# EaseEDA_Stand_Kovalenko.net
KiCad netlist of a schematic drawn in EasyEDA
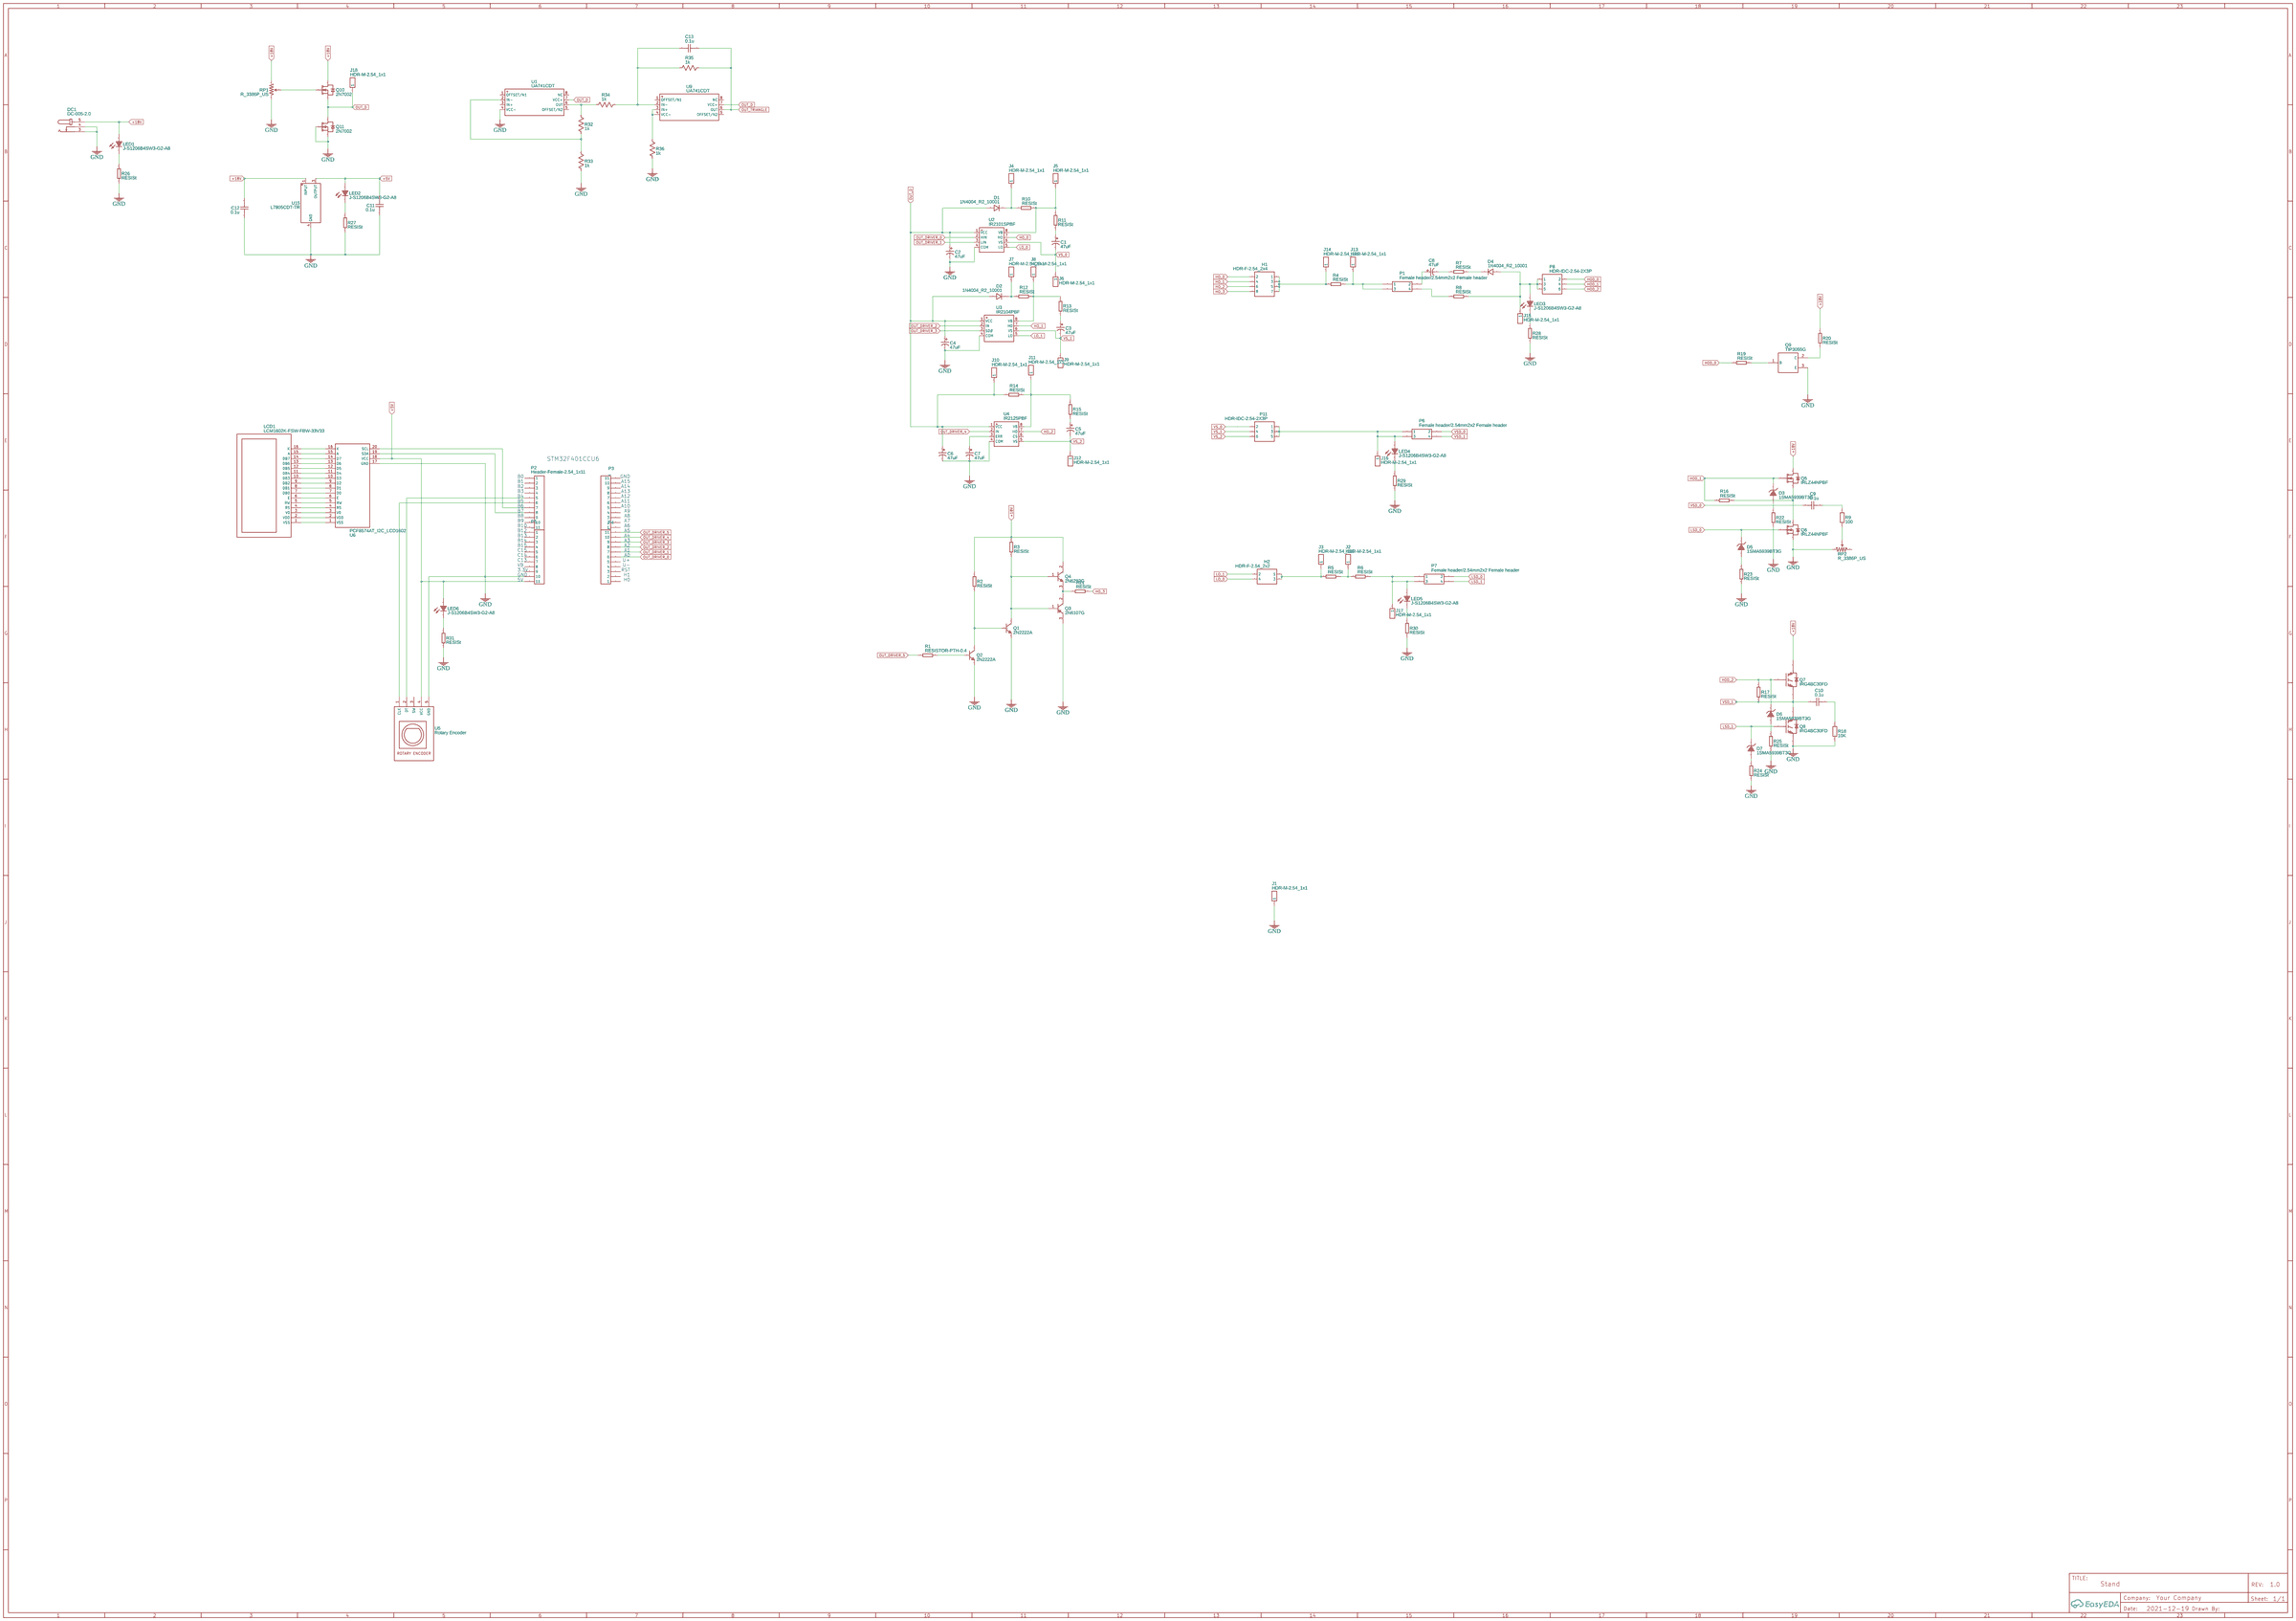
[diagram p0: schematic sheet]

(export (version "E")
  (design (tool "Eeschema 10.0.6"))
  (components
    (comp (ref "C1")
      (value "47uF")
      (fields
        (field (name "BOM_Manufacturer Part") "RD1J476M6L011PC380")
        (field (name "BOM_Supplier Part") "C238012")
      )
      (libsource (lib "") (part "RD1J476M6L011PC380"))
    )
    (comp (ref "C2")
      (value "47uF")
      (fields
        (field (name "BOM_Manufacturer Part") "RD1J476M6L011PC380")
        (field (name "BOM_Supplier Part") "C238012")
      )
      (libsource (lib "") (part "RD1J476M6L011PC380"))
    )
    (comp (ref "C3")
      (value "47uF")
      (fields
        (field (name "BOM_Manufacturer Part") "RD1J476M6L011PC380")
        (field (name "BOM_Supplier Part") "C238012")
      )
      (libsource (lib "") (part "RD1J476M6L011PC380"))
    )
    (comp (ref "C4")
      (value "47uF")
      (fields
        (field (name "BOM_Manufacturer Part") "RD1J476M6L011PC380")
        (field (name "BOM_Supplier Part") "C238012")
      )
      (libsource (lib "") (part "RD1J476M6L011PC380"))
    )
    (comp (ref "C5")
      (value "47uF")
      (fields
        (field (name "BOM_Manufacturer Part") "RD1J476M6L011PC380")
        (field (name "BOM_Supplier Part") "C238012")
      )
      (libsource (lib "") (part "RD1J476M6L011PC380"))
    )
    (comp (ref "C6")
      (value "47uF")
      (fields
        (field (name "BOM_Manufacturer Part") "RD1J476M6L011PC380")
        (field (name "BOM_Supplier Part") "C238012")
      )
      (libsource (lib "") (part "RD1J476M6L011PC380"))
    )
    (comp (ref "C7")
      (value "47uF")
      (fields
        (field (name "BOM_Manufacturer Part") "RD1J476M6L011PC380")
        (field (name "BOM_Supplier Part") "C238012")
      )
      (libsource (lib "") (part "RD1J476M6L011PC380"))
    )
    (comp (ref "C8")
      (value "47uF")
      (fields
        (field (name "BOM_Manufacturer Part") "RD1J476M6L011PC380")
        (field (name "BOM_Supplier Part") "C238012")
      )
      (libsource (lib "") (part "RD1J476M6L011PC380_1"))
    )
    (comp (ref "C9") (value "0.1u") (libsource (lib "") (part "C_0603_US")))
    (comp (ref "C10") (value "0.1u") (libsource (lib "") (part "C_0603_US")))
    (comp (ref "C11") (value "0.1u") (libsource (lib "") (part "C_0603_US_1")))
    (comp (ref "C12") (value "0.1u") (libsource (lib "") (part "C_0603_US_1")))
    (comp (ref "C13") (value "0.1u") (libsource (lib "") (part "C_0603_US_2")))
    (comp (ref "D1")
      (value "1N4004_R2_10001")
      (fields (field (name "BOM_Supplier Part") "C391322"))
      (libsource (lib "") (part "1N4004_R2_10001_1"))
    )
    (comp (ref "D2")
      (value "1N4004_R2_10001")
      (fields (field (name "BOM_Supplier Part") "C391322"))
      (libsource (lib "") (part "1N4004_R2_10001_1"))
    )
    (comp (ref "D3")
      (value "1SMA5939BT3G")
      (fields (field (name "BOM_Supplier Part") "C238874"))
      (libsource (lib "") (part "1SMA5939BT3G"))
    )
    (comp (ref "D4")
      (value "1N4004_R2_10001")
      (fields (field (name "BOM_Supplier Part") "C391322"))
      (libsource (lib "") (part "1N4004_R2_10001"))
    )
    (comp (ref "D5")
      (value "1SMA5939BT3G")
      (fields (field (name "BOM_Supplier Part") "C238874"))
      (libsource (lib "") (part "1SMA5939BT3G"))
    )
    (comp (ref "D6")
      (value "1SMA5939BT3G")
      (fields (field (name "BOM_Supplier Part") "C238874"))
      (libsource (lib "") (part "1SMA5939BT3G"))
    )
    (comp (ref "D7")
      (value "1SMA5939BT3G")
      (fields (field (name "BOM_Supplier Part") "C238874"))
      (libsource (lib "") (part "1SMA5939BT3G"))
    )
    (comp (ref "DC1")
      (value "DC-005-2.0")
      (fields (field (name "BOM_Supplier Part") "C521451"))
      (libsource (lib "") (part "DC-005-2.0"))
    )
    (comp (ref "H1")
      (value "HDR-F-2.54_2x4")
      (fields (field (name "BOM_Supplier Part") "C239344"))
      (libsource (lib "") (part "HDR-F-2.54_2x4"))
    )
    (comp (ref "H2")
      (value "HDR-F-2.54_2x2")
      (fields (field (name "BOM_Supplier Part") "C239342"))
      (libsource (lib "") (part "HDR-F-2.54_2x2"))
    )
    (comp (ref "J1")
      (value "HDR-M-2.54_1x1")
      (fields (field (name "BOM_Supplier Part") "C81276"))
      (libsource (lib "") (part "HDR-M-2.54_1x1"))
    )
    (comp (ref "J2")
      (value "HDR-M-2.54_1x1")
      (fields (field (name "BOM_Supplier Part") "C81276"))
      (libsource (lib "") (part "HDR-M-2.54_1x1"))
    )
    (comp (ref "J3")
      (value "HDR-M-2.54_1x1")
      (fields (field (name "BOM_Supplier Part") "C81276"))
      (libsource (lib "") (part "HDR-M-2.54_1x1"))
    )
    (comp (ref "J4")
      (value "HDR-M-2.54_1x1")
      (fields (field (name "BOM_Supplier Part") "C81276"))
      (libsource (lib "") (part "HDR-M-2.54_1x1"))
    )
    (comp (ref "J5")
      (value "HDR-M-2.54_1x1")
      (fields (field (name "BOM_Supplier Part") "C81276"))
      (libsource (lib "") (part "HDR-M-2.54_1x1"))
    )
    (comp (ref "J6")
      (value "HDR-M-2.54_1x1")
      (fields (field (name "BOM_Supplier Part") "C81276"))
      (libsource (lib "") (part "HDR-M-2.54_1x1_1"))
    )
    (comp (ref "J7")
      (value "HDR-M-2.54_1x1")
      (fields (field (name "BOM_Supplier Part") "C81276"))
      (libsource (lib "") (part "HDR-M-2.54_1x1"))
    )
    (comp (ref "J8")
      (value "HDR-M-2.54_1x1")
      (fields (field (name "BOM_Supplier Part") "C81276"))
      (libsource (lib "") (part "HDR-M-2.54_1x1"))
    )
    (comp (ref "J9")
      (value "HDR-M-2.54_1x1")
      (fields (field (name "BOM_Supplier Part") "C81276"))
      (libsource (lib "") (part "HDR-M-2.54_1x1_1"))
    )
    (comp (ref "J10")
      (value "HDR-M-2.54_1x1")
      (fields (field (name "BOM_Supplier Part") "C81276"))
      (libsource (lib "") (part "HDR-M-2.54_1x1"))
    )
    (comp (ref "J11")
      (value "HDR-M-2.54_1x1")
      (fields (field (name "BOM_Supplier Part") "C81276"))
      (libsource (lib "") (part "HDR-M-2.54_1x1"))
    )
    (comp (ref "J12")
      (value "HDR-M-2.54_1x1")
      (fields (field (name "BOM_Supplier Part") "C81276"))
      (libsource (lib "") (part "HDR-M-2.54_1x1_1"))
    )
    (comp (ref "J13")
      (value "HDR-M-2.54_1x1")
      (fields (field (name "BOM_Supplier Part") "C81276"))
      (libsource (lib "") (part "HDR-M-2.54_1x1"))
    )
    (comp (ref "J14")
      (value "HDR-M-2.54_1x1")
      (fields (field (name "BOM_Supplier Part") "C81276"))
      (libsource (lib "") (part "HDR-M-2.54_1x1"))
    )
    (comp (ref "J15")
      (value "HDR-M-2.54_1x1")
      (fields (field (name "BOM_Supplier Part") "C81276"))
      (libsource (lib "") (part "HDR-M-2.54_1x1_1"))
    )
    (comp (ref "J16")
      (value "HDR-M-2.54_1x1")
      (fields (field (name "BOM_Supplier Part") "C81276"))
      (libsource (lib "") (part "HDR-M-2.54_1x1_1"))
    )
    (comp (ref "J17")
      (value "HDR-M-2.54_1x1")
      (fields (field (name "BOM_Supplier Part") "C81276"))
      (libsource (lib "") (part "HDR-M-2.54_1x1_1"))
    )
    (comp (ref "J18")
      (value "HDR-M-2.54_1x1")
      (fields (field (name "BOM_Supplier Part") "C81276"))
      (libsource (lib "") (part "HDR-M-2.54_1x1"))
    )
    (comp (ref "LCD1")
      (value "LCM1602K-FSW-FBW-33V33")
      (fields (field (name "BOM_Supplier Part") "C83271"))
      (libsource (lib "") (part "LCM1602K-FSW-FBW-33V33"))
    )
    (comp (ref "LED1")
      (value "J-S1206B4SW3-G2-A8")
      (fields (field (name "BOM_Supplier Part") "C2917491"))
      (libsource (lib "") (part "J-S1206B4SW3-G2-A8"))
    )
    (comp (ref "LED2")
      (value "J-S1206B4SW3-G2-A8")
      (fields (field (name "BOM_Supplier Part") "C2917491"))
      (libsource (lib "") (part "J-S1206B4SW3-G2-A8"))
    )
    (comp (ref "LED3")
      (value "J-S1206B4SW3-G2-A8")
      (fields (field (name "BOM_Supplier Part") "C2917491"))
      (libsource (lib "") (part "J-S1206B4SW3-G2-A8"))
    )
    (comp (ref "LED4")
      (value "J-S1206B4SW3-G2-A8")
      (fields (field (name "BOM_Supplier Part") "C2917491"))
      (libsource (lib "") (part "J-S1206B4SW3-G2-A8"))
    )
    (comp (ref "LED5")
      (value "J-S1206B4SW3-G2-A8")
      (fields (field (name "BOM_Supplier Part") "C2917491"))
      (libsource (lib "") (part "J-S1206B4SW3-G2-A8"))
    )
    (comp (ref "LED6")
      (value "J-S1206B4SW3-G2-A8")
      (fields (field (name "BOM_Supplier Part") "C2917491"))
      (libsource (lib "") (part "J-S1206B4SW3-G2-A8"))
    )
    (comp (ref "P1")
      (value "Female header/2.54mm2x2 Female header")
      (fields (field (name "BOM_Supplier Part") "undefined"))
      (libsource (lib "") (part "Female header/2.54mm2x2 Female header"))
    )
    (comp (ref "P2")
      (value "Header-Female-2.54_1x11")
      (fields
        (field (name "BOM_Manufacturer Part") "Header-Female-2.54_1x10")
        (field (name "BOM_Supplier Part") "undefined")
      )
      (libsource (lib "") (part "Header-Female-2.54_1x11"))
    )
    (comp (ref "P3")
      (value "_")
      (fields
        (field (name "BOM_Manufacturer Part") "Header-Female-2.54_1x10")
        (field (name "BOM_Supplier Part") "undefined")
      )
      (libsource (lib "") (part "Header-Female-2.54_1x11_1"))
    )
    (comp (ref "P4")
      (value "_")
      (fields
        (field (name "BOM_Manufacturer Part") "Header-Female-2.54_1x10")
        (field (name "BOM_Supplier Part") "undefined")
      )
      (libsource (lib "") (part "Header-Female-2.54_1x11_1"))
    )
    (comp (ref "P5")
      (value "_")
      (fields
        (field (name "BOM_Manufacturer Part") "Header-Female-2.54_1x10")
        (field (name "BOM_Supplier Part") "undefined")
      )
      (libsource (lib "") (part "Header-Female-2.54_1x11"))
    )
    (comp (ref "P6")
      (value "Female header/2.54mm2x2 Female header")
      (fields (field (name "BOM_Supplier Part") "undefined"))
      (libsource (lib "") (part "Female header/2.54mm2x2 Female header"))
    )
    (comp (ref "P7")
      (value "Female header/2.54mm2x2 Female header")
      (fields (field (name "BOM_Supplier Part") "undefined"))
      (libsource (lib "") (part "Female header/2.54mm2x2 Female header"))
    )
    (comp (ref "P8")
      (value "HDR-IDC-2.54-2X3P")
      (fields
        (field (name "BOM_Manufacturer Part") "2X3 2.54mm IDC Box")
        (field (name "BOM_Supplier Part") "C11214")
      )
      (libsource (lib "") (part "HDR-IDC-2.54-2X3P_1"))
    )
    (comp (ref "P11")
      (value "HDR-IDC-2.54-2X3P")
      (fields
        (field (name "BOM_Manufacturer Part") "2X3 2.54mm IDC Box")
        (field (name "BOM_Supplier Part") "C11214")
      )
      (libsource (lib "") (part "HDR-IDC-2.54-2X3P"))
    )
    (comp (ref "Q1")
      (value "2N2222A")
      (fields (field (name "BOM_Supplier Part") "C358533"))
      (libsource (lib "") (part "2N2222A"))
    )
    (comp (ref "Q2")
      (value "2N2222A")
      (fields (field (name "BOM_Supplier Part") "C358533"))
      (libsource (lib "") (part "2N2222A"))
    )
    (comp (ref "Q3") (value "2N6107G") (libsource (lib "") (part "2N6107G")))
    (comp (ref "Q4") (value "2N6292G") (libsource (lib "") (part "2N6292G")))
    (comp (ref "Q5")
      (value "IRLZ44NPBF")
      (fields (field (name "BOM_Supplier Part") "C38774"))
      (libsource (lib "") (part "IRLZ44NPBF"))
    )
    (comp (ref "Q6")
      (value "IRLZ44NPBF")
      (fields (field (name "BOM_Supplier Part") "C38774"))
      (libsource (lib "") (part "IRLZ44NPBF"))
    )
    (comp (ref "Q7") (value "IRG4BC30FD") (libsource (lib "") (part "IRG4BC30FD")))
    (comp (ref "Q8") (value "IRG4BC30FD") (libsource (lib "") (part "IRG4BC30FD")))
    (comp (ref "Q9") (value "TIP3055G") (libsource (lib "") (part "TIP3055G")))
    (comp (ref "Q10")
      (value "2N7002")
      (fields (field (name "BOM_Manufacturer Part") "2N7002,215") (field (name "BOM_Supplier Part") "C65189"))
      (libsource (lib "") (part "2N7002"))
    )
    (comp (ref "Q11")
      (value "2N7002")
      (fields (field (name "BOM_Manufacturer Part") "2N7002,215") (field (name "BOM_Supplier Part") "C65189"))
      (libsource (lib "") (part "2N7002"))
    )
    (comp (ref "R1") (value "RESISTOR-PTH-0.4") (libsource (lib "") (part "RESISTOR-PTH-0.4_3")))
    (comp (ref "R2") (value "RESISt") (libsource (lib "") (part "RESISTOR-PTH-0.4_2")))
    (comp (ref "R3") (value "RESISt") (libsource (lib "") (part "RESISTOR-PTH-0.4_2")))
    (comp (ref "R4") (value "RESISt") (libsource (lib "") (part "RESISTOR-PTH-0.4_1")))
    (comp (ref "R5") (value "RESISt") (libsource (lib "") (part "RESISTOR-PTH-0.4_1")))
    (comp (ref "R6") (value "RESISt") (libsource (lib "") (part "RESISTOR-PTH-0.4_1")))
    (comp (ref "R7") (value "RESISt") (libsource (lib "") (part "RESISTOR-PTH-0.4_1")))
    (comp (ref "R8") (value "RESISt") (libsource (lib "") (part "RESISTOR-PTH-0.4_1")))
    (comp (ref "R9")
      (value "100")
      (fields
        (field (name "BOM_Manufacturer Part") "EWWR0010J10K0T9")
        (field (name "BOM_Supplier Part") "C349083")
      )
      (libsource (lib "") (part "EWWR0010J10K0T9"))
    )
    (comp (ref "R10") (value "RESISt") (libsource (lib "") (part "RESISTOR-PTH-0.4_3")))
    (comp (ref "R11") (value "RESISt") (libsource (lib "") (part "RESISTOR-PTH-0.4_2")))
    (comp (ref "R12") (value "RESISt") (libsource (lib "") (part "RESISTOR-PTH-0.4_3")))
    (comp (ref "R13") (value "RESISt") (libsource (lib "") (part "RESISTOR-PTH-0.4")))
    (comp (ref "R14") (value "RESISt") (libsource (lib "") (part "RESISTOR-PTH-0.4_3")))
    (comp (ref "R15") (value "RESISt") (libsource (lib "") (part "RESISTOR-PTH-0.4")))
    (comp (ref "R16") (value "RESISt") (libsource (lib "") (part "RESISTOR-PTH-0.4_1")))
    (comp (ref "R17") (value "RESISt") (libsource (lib "") (part "RESISTOR-PTH-0.4")))
    (comp (ref "R18")
      (value "10K")
      (fields
        (field (name "BOM_Manufacturer Part") "EWWR0010J10K0T9")
        (field (name "BOM_Supplier Part") "C349083")
      )
      (libsource (lib "") (part "EWWR0010J10K0T9"))
    )
    (comp (ref "R19") (value "RESISt") (libsource (lib "") (part "RESISTOR-PTH-0.4_1")))
    (comp (ref "R20") (value "RESISt") (libsource (lib "") (part "RESISTOR-PTH-0.4")))
    (comp (ref "R21") (value "RESISt") (libsource (lib "") (part "RESISTOR-PTH-0.4_3")))
    (comp (ref "R22") (value "RESISt") (libsource (lib "") (part "RESISTOR-PTH-0.4")))
    (comp (ref "R23") (value "RESISt") (libsource (lib "") (part "RESISTOR-PTH-0.4")))
    (comp (ref "R24") (value "RESISt") (libsource (lib "") (part "RESISTOR-PTH-0.4")))
    (comp (ref "R25") (value "RESISt") (libsource (lib "") (part "RESISTOR-PTH-0.4")))
    (comp (ref "R26") (value "RESISt") (libsource (lib "") (part "RESISTOR-PTH-0.4")))
    (comp (ref "R27") (value "RESISt") (libsource (lib "") (part "RESISTOR-PTH-0.4")))
    (comp (ref "R28") (value "RESISt") (libsource (lib "") (part "RESISTOR-PTH-0.4")))
    (comp (ref "R29") (value "RESISt") (libsource (lib "") (part "RESISTOR-PTH-0.4")))
    (comp (ref "R30") (value "RESISt") (libsource (lib "") (part "RESISTOR-PTH-0.4")))
    (comp (ref "R31") (value "RESISt") (libsource (lib "") (part "RESISTOR-PTH-0.4")))
    (comp (ref "R32") (value "1k") (libsource (lib "") (part "R_0603_US_2")))
    (comp (ref "R33") (value "1k") (libsource (lib "") (part "R_0603_US_2")))
    (comp (ref "R34") (value "1k") (libsource (lib "") (part "R_0603_US")))
    (comp (ref "R35") (value "1k") (libsource (lib "") (part "R_0603_US")))
    (comp (ref "R36") (value "1k") (libsource (lib "") (part "R_0603_US_1")))
    (comp (ref "RP1") (value "R_3386P_US") (libsource (lib "") (part "R_3386P_US")))
    (comp (ref "RP2") (value "R_3386P_US") (libsource (lib "") (part "R_3386P_US_1")))
    (comp (ref "U1")
      (value "UA741CDT")
      (fields (field (name "BOM_Supplier Part") "C7111"))
      (libsource (lib "") (part "UA741CDT"))
    )
    (comp (ref "U2")
      (value "IR2101SPBF")
      (fields (field (name "BOM_Supplier Part") "C537541"))
      (libsource (lib "") (part "IR2101SPBF"))
    )
    (comp (ref "U3")
      (value "IR2104PBF")
      (fields (field (name "BOM_Supplier Part") "C2959"))
      (libsource (lib "") (part "IR2104PBF"))
    )
    (comp (ref "U4")
      (value "IR2125PBF")
      (fields (field (name "BOM_Supplier Part") "C537562"))
      (libsource (lib "") (part "IR2125PBF"))
    )
    (comp (ref "U5")
      (value "Rotary Encoder")
      (fields (field (name "BOM_Manufacturer Part") "KY-040"))
      (libsource (lib "") (part "Rotary Encoder"))
    )
    (comp (ref "U6")
      (value "PCF8574AT_I2C_LCD1602")
      (fields (field (name "BOM_Manufacturer Part") "PCF8574AT_modul"))
      (libsource (lib "") (part "PCF8574AT_I2C_LCD1602"))
    )
    (comp (ref "U9")
      (value "UA741CDT")
      (fields (field (name "BOM_Supplier Part") "C7111"))
      (libsource (lib "") (part "UA741CDT"))
    )
    (comp (ref "U15")
      (value "L7805CDT-TR")
      (fields (field (name "BOM_Supplier Part") "C310413"))
      (libsource (lib "") (part "L7805CDT-TR"))
    )
  )
  (nets
    (net (code "1") (name "+5V") (class "Default")
      (node (ref "C11") (pin "2") (pinfunction "2_2") (pintype "unspecified"))
      (node (ref "LED2") (pin "2") (pinfunction "A_2") (pintype "input"))
      (node (ref "LED6") (pin "2") (pinfunction "A_2") (pintype "input"))
      (node (ref "P5") (pin "11") (pinfunction "11_11") (pintype "input"))
      (node (ref "U15") (pin "3") (pinfunction "OUTPUT_3") (pintype "unspecified"))
      (node (ref "U5") (pin "4") (pinfunction "VCC_4") (pintype "unspecified"))
      (node (ref "U6") (pin "18") (pinfunction "VCC_18") (pintype "unspecified"))
    )
    (net (code "2") (name "+18V") (class "Default")
      (node (ref "C12") (pin "2") (pinfunction "2_2") (pintype "unspecified"))
      (node (ref "DC1") (pin "5") (pinfunction "5_5") (pintype "unspecified"))
      (node (ref "LED1") (pin "2") (pinfunction "A_2") (pintype "input"))
      (node (ref "Q10") (pin "3") (pinfunction "D_3") (pintype "unspecified"))
      (node (ref "Q4") (pin "2") (pinfunction "C_2") (pintype "unspecified"))
      (node (ref "Q5") (pin "2") (pinfunction "D_2") (pintype "unspecified"))
      (node (ref "Q7") (pin "2") (pinfunction "C_2") (pintype "unspecified"))
      (node (ref "R2") (pin "1") (pinfunction "1_1") (pintype "unspecified"))
      (node (ref "R20") (pin "2") (pinfunction "2_2") (pintype "unspecified"))
      (node (ref "R3") (pin "1") (pinfunction "1_1") (pintype "unspecified"))
      (node (ref "RP1") (pin "1") (pinfunction "1_1") (pintype "unspecified"))
      (node (ref "U15") (pin "1") (pinfunction "INPUT_1") (pintype "unspecified"))
    )
    (net (code "3") (name "GND") (class "Default")
      (node (ref "C11") (pin "1") (pinfunction "1_1") (pintype "unspecified"))
      (node (ref "C12") (pin "1") (pinfunction "1_1") (pintype "unspecified"))
      (node (ref "C2") (pin "2") (pinfunction "2_2") (pintype "input"))
      (node (ref "C4") (pin "2") (pinfunction "2_2") (pintype "input"))
      (node (ref "C6") (pin "2") (pinfunction "2_2") (pintype "input"))
      (node (ref "C7") (pin "2") (pinfunction "2_2") (pintype "input"))
      (node (ref "DC1") (pin "3") (pinfunction "3_3") (pintype "unspecified"))
      (node (ref "DC1") (pin "4") (pinfunction "4_4") (pintype "unspecified"))
      (node (ref "J1") (pin "1") (pinfunction "1_1") (pintype "input"))
      (node (ref "P5") (pin "10") (pinfunction "10_10") (pintype "input"))
      (node (ref "Q1") (pin "3") (pinfunction "E_3") (pintype "unspecified"))
      (node (ref "Q11") (pin "1") (pinfunction "G_1") (pintype "unspecified"))
      (node (ref "Q11") (pin "2") (pinfunction "S_2") (pintype "unspecified"))
      (node (ref "Q2") (pin "3") (pinfunction "E_3") (pintype "unspecified"))
      (node (ref "Q3") (pin "3") (pinfunction "E_3") (pintype "unspecified"))
      (node (ref "Q6") (pin "3") (pinfunction "S_3") (pintype "unspecified"))
      (node (ref "Q8") (pin "3") (pinfunction "E_3") (pintype "unspecified"))
      (node (ref "Q9") (pin "3") (pinfunction "E_3") (pintype "unspecified"))
      (node (ref "R18") (pin "2") (pinfunction "2_2") (pintype "unspecified"))
      (node (ref "R22") (pin "1") (pinfunction "1_1") (pintype "unspecified"))
      (node (ref "R23") (pin "1") (pinfunction "1_1") (pintype "unspecified"))
      (node (ref "R24") (pin "1") (pinfunction "1_1") (pintype "unspecified"))
      (node (ref "R25") (pin "1") (pinfunction "1_1") (pintype "unspecified"))
      (node (ref "R26") (pin "1") (pinfunction "1_1") (pintype "unspecified"))
      (node (ref "R27") (pin "1") (pinfunction "1_1") (pintype "unspecified"))
      (node (ref "R28") (pin "1") (pinfunction "1_1") (pintype "unspecified"))
      (node (ref "R29") (pin "1") (pinfunction "1_1") (pintype "unspecified"))
      (node (ref "R30") (pin "1") (pinfunction "1_1") (pintype "unspecified"))
      (node (ref "R31") (pin "1") (pinfunction "1_1") (pintype "unspecified"))
      (node (ref "R33") (pin "1") (pinfunction "1_1") (pintype "unspecified"))
      (node (ref "R36") (pin "2") (pinfunction "2_2") (pintype "unspecified"))
      (node (ref "RP1") (pin "3") (pinfunction "3_3") (pintype "unspecified"))
      (node (ref "RP2") (pin "1") (pinfunction "1_1") (pintype "unspecified"))
      (node (ref "U1") (pin "4") (pinfunction "VCC-_4") (pintype "unspecified"))
      (node (ref "U15") (pin "4") (pinfunction "GND_4") (pintype "unspecified"))
      (node (ref "U2") (pin "4") (pinfunction "COM_4") (pintype "unspecified"))
      (node (ref "U3") (pin "4") (pinfunction "COM_4") (pintype "unspecified"))
      (node (ref "U4") (pin "4") (pinfunction "COM_4") (pintype "unspecified"))
      (node (ref "U5") (pin "5") (pinfunction "GND_5") (pintype "unspecified"))
      (node (ref "U6") (pin "17") (pinfunction "GND_17") (pintype "unspecified"))
    )
    (net (code "4") (name "HOD_0") (class "Default")
      (node (ref "P8") (pin "2") (pinfunction "2_2") (pintype "unspecified"))
      (node (ref "R19") (pin "2") (pinfunction "2_2") (pintype "unspecified"))
    )
    (net (code "5") (name "HOD_1") (class "Default")
      (node (ref "D3") (pin "1") (pinfunction "C_1") (pintype "unspecified"))
      (node (ref "P8") (pin "4") (pinfunction "4_4") (pintype "unspecified"))
      (node (ref "Q5") (pin "1") (pinfunction "G_1") (pintype "unspecified"))
      (node (ref "R16") (pin "2") (pinfunction "2_2") (pintype "unspecified"))
    )
    (net (code "6") (name "HOD_2") (class "Default")
      (node (ref "D6") (pin "1") (pinfunction "C_1") (pintype "unspecified"))
      (node (ref "P8") (pin "6") (pinfunction "6_6") (pintype "unspecified"))
      (node (ref "Q7") (pin "1") (pinfunction "G_1") (pintype "unspecified"))
      (node (ref "R17") (pin "2") (pinfunction "2_2") (pintype "unspecified"))
    )
    (net (code "7") (name "HO_0") (class "Default")
      (node (ref "H1") (pin "2") (pinfunction "2_2") (pintype "unspecified"))
      (node (ref "U2") (pin "7") (pinfunction "HO_7") (pintype "unspecified"))
    )
    (net (code "8") (name "HO_1") (class "Default")
      (node (ref "H1") (pin "4") (pinfunction "4_4") (pintype "unspecified"))
      (node (ref "U3") (pin "7") (pinfunction "HO_7") (pintype "unspecified"))
    )
    (net (code "9") (name "HO_2") (class "Default")
      (node (ref "H1") (pin "6") (pinfunction "6_6") (pintype "unspecified"))
      (node (ref "U4") (pin "7") (pinfunction "HO_7") (pintype "unspecified"))
    )
    (net (code "10") (name "HO_3") (class "Default")
      (node (ref "H1") (pin "8") (pinfunction "8_8") (pintype "unspecified"))
      (node (ref "R21") (pin "2") (pinfunction "2_2") (pintype "unspecified"))
    )
    (net (code "11") (name "LO_0") (class "Default")
      (node (ref "H2") (pin "4") (pinfunction "4_4") (pintype "unspecified"))
      (node (ref "U2") (pin "5") (pinfunction "LO_5") (pintype "unspecified"))
    )
    (net (code "12") (name "LO_1") (class "Default")
      (node (ref "H2") (pin "2") (pinfunction "2_2") (pintype "unspecified"))
      (node (ref "U3") (pin "5") (pinfunction "LO_5") (pintype "unspecified"))
    )
    (net (code "13") (name "LSD_0") (class "Default")
      (node (ref "D5") (pin "1") (pinfunction "C_1") (pintype "unspecified"))
      (node (ref "P7") (pin "2") (pinfunction "2_2") (pintype "input"))
      (node (ref "Q6") (pin "1") (pinfunction "G_1") (pintype "unspecified"))
    )
    (net (code "14") (name "LSD_1") (class "Default")
      (node (ref "D7") (pin "1") (pinfunction "C_1") (pintype "unspecified"))
      (node (ref "P7") (pin "4") (pinfunction "4_4") (pintype "input"))
      (node (ref "Q8") (pin "1") (pinfunction "G_1") (pintype "unspecified"))
    )
    (net (code "15") (name "Net-(C1-Pad1)") (class "Default")
      (node (ref "C1") (pin "1") (pinfunction "1_1") (pintype "input"))
      (node (ref "R11") (pin "2") (pinfunction "2_2") (pintype "unspecified"))
    )
    (net (code "16") (name "Net-(C3-Pad1)") (class "Default")
      (node (ref "C3") (pin "1") (pinfunction "1_1") (pintype "input"))
      (node (ref "R13") (pin "1") (pinfunction "1_1") (pintype "unspecified"))
    )
    (net (code "17") (name "Net-(C5-Pad1)") (class "Default")
      (node (ref "C5") (pin "1") (pinfunction "1_1") (pintype "input"))
      (node (ref "R15") (pin "1") (pinfunction "1_1") (pintype "unspecified"))
    )
    (net (code "18") (name "Net-(C8-Pad1)") (class "Default")
      (node (ref "C8") (pin "1") (pinfunction "1_1") (pintype "input"))
      (node (ref "P1") (pin "2") (pinfunction "2_2") (pintype "input"))
    )
    (net (code "19") (name "Net-(C8-Pad2)") (class "Default")
      (node (ref "C8") (pin "2") (pinfunction "2_2") (pintype "input"))
      (node (ref "R7") (pin "2") (pinfunction "2_2") (pintype "unspecified"))
    )
    (net (code "20") (name "Net-(C9-Pad2)") (class "Default")
      (node (ref "C9") (pin "2") (pinfunction "2_2") (pintype "unspecified"))
      (node (ref "R9") (pin "1") (pinfunction "1_1") (pintype "unspecified"))
    )
    (net (code "21") (name "Net-(C10-Pad2)") (class "Default")
      (node (ref "C10") (pin "2") (pinfunction "2_2") (pintype "unspecified"))
      (node (ref "R18") (pin "1") (pinfunction "1_1") (pintype "unspecified"))
    )
    (net (code "22") (name "Net-(D1-C)") (class "Default")
      (node (ref "D1") (pin "1") (pinfunction "C_1") (pintype "unspecified"))
      (node (ref "J4") (pin "1") (pinfunction "1_1") (pintype "input"))
      (node (ref "R10") (pin "1") (pinfunction "1_1") (pintype "unspecified"))
    )
    (net (code "23") (name "Net-(D2-C)") (class "Default")
      (node (ref "D2") (pin "1") (pinfunction "C_1") (pintype "unspecified"))
      (node (ref "J7") (pin "1") (pinfunction "1_1") (pintype "input"))
      (node (ref "R12") (pin "1") (pinfunction "1_1") (pintype "unspecified"))
    )
    (net (code "24") (name "Net-(D3-A)") (class "Default")
      (node (ref "D3") (pin "2") (pinfunction "A_2") (pintype "unspecified"))
      (node (ref "R22") (pin "2") (pinfunction "2_2") (pintype "unspecified"))
    )
    (net (code "25") (name "Net-(D4-A)") (class "Default")
      (node (ref "D4") (pin "2") (pinfunction "A_2") (pintype "unspecified"))
      (node (ref "J15") (pin "1") (pinfunction "1_1") (pintype "input"))
      (node (ref "LED3") (pin "2") (pinfunction "A_2") (pintype "input"))
      (node (ref "P8") (pin "1") (pinfunction "1_1") (pintype "unspecified"))
      (node (ref "P8") (pin "3") (pinfunction "3_3") (pintype "unspecified"))
      (node (ref "P8") (pin "5") (pinfunction "5_5") (pintype "unspecified"))
      (node (ref "R8") (pin "1") (pinfunction "1_1") (pintype "unspecified"))
    )
    (net (code "26") (name "Net-(D4-C)") (class "Default")
      (node (ref "D4") (pin "1") (pinfunction "C_1") (pintype "unspecified"))
      (node (ref "R7") (pin "1") (pinfunction "1_1") (pintype "unspecified"))
    )
    (net (code "27") (name "Net-(D5-A)") (class "Default")
      (node (ref "D5") (pin "2") (pinfunction "A_2") (pintype "unspecified"))
      (node (ref "R23") (pin "2") (pinfunction "2_2") (pintype "unspecified"))
    )
    (net (code "28") (name "Net-(D6-A)") (class "Default")
      (node (ref "D6") (pin "2") (pinfunction "A_2") (pintype "unspecified"))
      (node (ref "R25") (pin "2") (pinfunction "2_2") (pintype "unspecified"))
    )
    (net (code "29") (name "Net-(D7-A)") (class "Default")
      (node (ref "D7") (pin "2") (pinfunction "A_2") (pintype "unspecified"))
      (node (ref "R24") (pin "2") (pinfunction "2_2") (pintype "unspecified"))
    )
    (net (code "30") (name "Net-(H1-Pad1)") (class "Default")
      (node (ref "H1") (pin "1") (pinfunction "1_1") (pintype "unspecified"))
      (node (ref "H1") (pin "3") (pinfunction "3_3") (pintype "unspecified"))
      (node (ref "H1") (pin "5") (pinfunction "5_5") (pintype "unspecified"))
      (node (ref "H1") (pin "7") (pinfunction "7_7") (pintype "unspecified"))
      (node (ref "J14") (pin "1") (pinfunction "1_1") (pintype "input"))
      (node (ref "R4") (pin "2") (pinfunction "2_2") (pintype "unspecified"))
    )
    (net (code "31") (name "Net-(H2-Pad1)") (class "Default")
      (node (ref "H2") (pin "1") (pinfunction "1_1") (pintype "unspecified"))
      (node (ref "H2") (pin "3") (pinfunction "3_3") (pintype "unspecified"))
      (node (ref "J3") (pin "1") (pinfunction "1_1") (pintype "input"))
      (node (ref "R5") (pin "2") (pinfunction "2_2") (pintype "unspecified"))
    )
    (net (code "32") (name "Net-(J2-Pad1)") (class "Default")
      (node (ref "J2") (pin "1") (pinfunction "1_1") (pintype "input"))
      (node (ref "R5") (pin "1") (pinfunction "1_1") (pintype "unspecified"))
      (node (ref "R6") (pin "2") (pinfunction "2_2") (pintype "unspecified"))
    )
    (net (code "33") (name "Net-(J13-Pad1)") (class "Default")
      (node (ref "J13") (pin "1") (pinfunction "1_1") (pintype "input"))
      (node (ref "P1") (pin "1") (pinfunction "1_1") (pintype "input"))
      (node (ref "P1") (pin "3") (pinfunction "3_3") (pintype "input"))
      (node (ref "R4") (pin "1") (pinfunction "1_1") (pintype "unspecified"))
    )
    (net (code "34") (name "Net-(LCD1-A)") (class "Default")
      (node (ref "LCD1") (pin "15") (pinfunction "A_15") (pintype "unspecified"))
      (node (ref "U6") (pin "15") (pinfunction "A_15") (pintype "unspecified"))
    )
    (net (code "35") (name "Net-(LCD1-DB0)") (class "Default")
      (node (ref "LCD1") (pin "7") (pinfunction "DB0_7") (pintype "unspecified"))
      (node (ref "U6") (pin "7") (pinfunction "D0_7") (pintype "unspecified"))
    )
    (net (code "36") (name "Net-(LCD1-DB1)") (class "Default")
      (node (ref "LCD1") (pin "8") (pinfunction "DB1_8") (pintype "unspecified"))
      (node (ref "U6") (pin "8") (pinfunction "D1_8") (pintype "unspecified"))
    )
    (net (code "37") (name "Net-(LCD1-DB2)") (class "Default")
      (node (ref "LCD1") (pin "9") (pinfunction "DB2_9") (pintype "unspecified"))
      (node (ref "U6") (pin "9") (pinfunction "D2_9") (pintype "unspecified"))
    )
    (net (code "38") (name "Net-(LCD1-DB3)") (class "Default")
      (node (ref "LCD1") (pin "10") (pinfunction "DB3_10") (pintype "unspecified"))
      (node (ref "U6") (pin "10") (pinfunction "D3_10") (pintype "unspecified"))
    )
    (net (code "39") (name "Net-(LCD1-DB4)") (class "Default")
      (node (ref "LCD1") (pin "11") (pinfunction "DB4_11") (pintype "unspecified"))
      (node (ref "U6") (pin "11") (pinfunction "D4_11") (pintype "unspecified"))
    )
    (net (code "40") (name "Net-(LCD1-DB5)") (class "Default")
      (node (ref "LCD1") (pin "12") (pinfunction "DB5_12") (pintype "unspecified"))
      (node (ref "U6") (pin "12") (pinfunction "D5_12") (pintype "unspecified"))
    )
    (net (code "41") (name "Net-(LCD1-DB6)") (class "Default")
      (node (ref "LCD1") (pin "13") (pinfunction "DB6_13") (pintype "unspecified"))
      (node (ref "U6") (pin "13") (pinfunction "D6_13") (pintype "unspecified"))
    )
    (net (code "42") (name "Net-(LCD1-DB7)") (class "Default")
      (node (ref "LCD1") (pin "14") (pinfunction "DB7_14") (pintype "unspecified"))
      (node (ref "U6") (pin "14") (pinfunction "D7_14") (pintype "unspecified"))
    )
    (net (code "43") (name "Net-(LCD1-E)") (class "Default")
      (node (ref "LCD1") (pin "6") (pinfunction "E_6") (pintype "unspecified"))
      (node (ref "U6") (pin "6") (pinfunction "E_6") (pintype "unspecified"))
    )
    (net (code "44") (name "Net-(LCD1-K)") (class "Default")
      (node (ref "LCD1") (pin "16") (pinfunction "K_16") (pintype "unspecified"))
      (node (ref "U6") (pin "16") (pinfunction "K_16") (pintype "unspecified"))
    )
    (net (code "45") (name "Net-(LCD1-RS)") (class "Default")
      (node (ref "LCD1") (pin "4") (pinfunction "RS_4") (pintype "unspecified"))
      (node (ref "U6") (pin "4") (pinfunction "RS_4") (pintype "unspecified"))
    )
    (net (code "46") (name "Net-(LCD1-RW)") (class "Default")
      (node (ref "LCD1") (pin "5") (pinfunction "RW_5") (pintype "unspecified"))
      (node (ref "U6") (pin "5") (pinfunction "RW_5") (pintype "unspecified"))
    )
    (net (code "47") (name "Net-(LCD1-V0)") (class "Default")
      (node (ref "LCD1") (pin "3") (pinfunction "V0_3") (pintype "unspecified"))
      (node (ref "U6") (pin "3") (pinfunction "V0_3") (pintype "unspecified"))
    )
    (net (code "48") (name "Net-(LCD1-VDD)") (class "Default")
      (node (ref "LCD1") (pin "2") (pinfunction "VDD_2") (pintype "unspecified"))
      (node (ref "U6") (pin "2") (pinfunction "VDD_2") (pintype "unspecified"))
    )
    (net (code "49") (name "Net-(LCD1-VSS)") (class "Default")
      (node (ref "LCD1") (pin "1") (pinfunction "VSS_1") (pintype "unspecified"))
      (node (ref "U6") (pin "1") (pinfunction "VSS_1") (pintype "unspecified"))
    )
    (net (code "50") (name "Net-(LED1-K)") (class "Default")
      (node (ref "LED1") (pin "1") (pinfunction "K_1") (pintype "input"))
      (node (ref "R26") (pin "2") (pinfunction "2_2") (pintype "unspecified"))
    )
    (net (code "51") (name "Net-(LED2-K)") (class "Default")
      (node (ref "LED2") (pin "1") (pinfunction "K_1") (pintype "input"))
      (node (ref "R27") (pin "2") (pinfunction "2_2") (pintype "unspecified"))
    )
    (net (code "52") (name "Net-(LED3-K)") (class "Default")
      (node (ref "LED3") (pin "1") (pinfunction "K_1") (pintype "input"))
      (node (ref "R28") (pin "2") (pinfunction "2_2") (pintype "unspecified"))
    )
    (net (code "53") (name "Net-(LED4-A)") (class "Default")
      (node (ref "J16") (pin "1") (pinfunction "1_1") (pintype "input"))
      (node (ref "LED4") (pin "2") (pinfunction "A_2") (pintype "input"))
      (node (ref "P11") (pin "1") (pinfunction "1_1") (pintype "unspecified"))
      (node (ref "P11") (pin "3") (pinfunction "3_3") (pintype "unspecified"))
      (node (ref "P11") (pin "5") (pinfunction "5_5") (pintype "unspecified"))
      (node (ref "P6") (pin "1") (pinfunction "1_1") (pintype "input"))
      (node (ref "P6") (pin "3") (pinfunction "3_3") (pintype "input"))
    )
    (net (code "54") (name "Net-(LED4-K)") (class "Default")
      (node (ref "LED4") (pin "1") (pinfunction "K_1") (pintype "input"))
      (node (ref "R29") (pin "2") (pinfunction "2_2") (pintype "unspecified"))
    )
    (net (code "55") (name "Net-(LED5-A)") (class "Default")
      (node (ref "J17") (pin "1") (pinfunction "1_1") (pintype "input"))
      (node (ref "LED5") (pin "2") (pinfunction "A_2") (pintype "input"))
      (node (ref "P7") (pin "1") (pinfunction "1_1") (pintype "input"))
      (node (ref "P7") (pin "3") (pinfunction "3_3") (pintype "input"))
      (node (ref "R6") (pin "1") (pinfunction "1_1") (pintype "unspecified"))
    )
    (net (code "56") (name "Net-(LED5-K)") (class "Default")
      (node (ref "LED5") (pin "1") (pinfunction "K_1") (pintype "input"))
      (node (ref "R30") (pin "2") (pinfunction "2_2") (pintype "unspecified"))
    )
    (net (code "57") (name "Net-(LED6-K)") (class "Default")
      (node (ref "LED6") (pin "1") (pinfunction "K_1") (pintype "input"))
      (node (ref "R31") (pin "2") (pinfunction "2_2") (pintype "unspecified"))
    )
    (net (code "58") (name "Net-(P1-Pad4)") (class "Default")
      (node (ref "P1") (pin "4") (pinfunction "4_4") (pintype "input"))
      (node (ref "R8") (pin "2") (pinfunction "2_2") (pintype "unspecified"))
    )
    (net (code "59") (name "Net-(Q1-B)") (class "Default")
      (node (ref "Q1") (pin "2") (pinfunction "B_2") (pintype "unspecified"))
      (node (ref "Q2") (pin "1") (pinfunction "C_1") (pintype "unspecified"))
      (node (ref "R2") (pin "2") (pinfunction "2_2") (pintype "unspecified"))
    )
    (net (code "60") (name "Net-(Q1-C)") (class "Default")
      (node (ref "Q1") (pin "1") (pinfunction "C_1") (pintype "unspecified"))
      (node (ref "Q3") (pin "1") (pinfunction "B_1") (pintype "unspecified"))
      (node (ref "Q4") (pin "1") (pinfunction "B_1") (pintype "unspecified"))
      (node (ref "R3") (pin "2") (pinfunction "2_2") (pintype "unspecified"))
    )
    (net (code "61") (name "Net-(Q2-B)") (class "Default")
      (node (ref "Q2") (pin "2") (pinfunction "B_2") (pintype "unspecified"))
      (node (ref "R1") (pin "2") (pinfunction "2_2") (pintype "unspecified"))
    )
    (net (code "62") (name "Net-(Q3-C)") (class "Default")
      (node (ref "Q3") (pin "2") (pinfunction "C_2") (pintype "unspecified"))
      (node (ref "Q4") (pin "3") (pinfunction "E_3") (pintype "unspecified"))
      (node (ref "R21") (pin "1") (pinfunction "1_1") (pintype "unspecified"))
    )
    (net (code "63") (name "Net-(Q5-S)") (class "Default")
      (node (ref "Q5") (pin "3") (pinfunction "S_3") (pintype "unspecified"))
      (node (ref "Q6") (pin "2") (pinfunction "D_2") (pintype "unspecified"))
      (node (ref "R16") (pin "1") (pinfunction "1_1") (pintype "unspecified"))
    )
    (net (code "64") (name "Net-(Q9-B)") (class "Default")
      (node (ref "Q9") (pin "1") (pinfunction "B_1") (pintype "unspecified"))
      (node (ref "R19") (pin "1") (pinfunction "1_1") (pintype "unspecified"))
    )
    (net (code "65") (name "Net-(Q9-C)") (class "Default")
      (node (ref "Q9") (pin "2") (pinfunction "C_2") (pintype "unspecified"))
      (node (ref "R20") (pin "1") (pinfunction "1_1") (pintype "unspecified"))
    )
    (net (code "66") (name "Net-(Q10-G)") (class "Default")
      (node (ref "Q10") (pin "1") (pinfunction "G_1") (pintype "unspecified"))
      (node (ref "RP1") (pin "2") (pinfunction "2_2") (pintype "unspecified"))
    )
    (net (code "67") (name "Net-(R9-Pad2)") (class "Default")
      (node (ref "R9") (pin "2") (pinfunction "2_2") (pintype "unspecified"))
      (node (ref "RP2") (pin "2") (pinfunction "2_2") (pintype "unspecified"))
    )
    (net (code "68") (name "Net-(U1-IN-)") (class "Default")
      (node (ref "R32") (pin "1") (pinfunction "1_1") (pintype "unspecified"))
      (node (ref "R33") (pin "2") (pinfunction "2_2") (pintype "unspecified"))
      (node (ref "U1") (pin "2") (pinfunction "IN-_2") (pintype "unspecified"))
    )
    (net (code "69") (name "Net-(U1-OUT)") (class "Default")
      (node (ref "R32") (pin "2") (pinfunction "2_2") (pintype "unspecified"))
      (node (ref "R34") (pin "2") (pinfunction "2_2") (pintype "unspecified"))
      (node (ref "U1") (pin "6") (pinfunction "OUT_6") (pintype "unspecified"))
    )
    (net (code "70") (name "Net-(U2-VB)") (class "Default")
      (node (ref "J5") (pin "1") (pinfunction "1_1") (pintype "input"))
      (node (ref "R10") (pin "2") (pinfunction "2_2") (pintype "unspecified"))
      (node (ref "R11") (pin "1") (pinfunction "1_1") (pintype "unspecified"))
      (node (ref "U2") (pin "8") (pinfunction "VB_8") (pintype "unspecified"))
    )
    (net (code "71") (name "Net-(U3-VB)") (class "Default")
      (node (ref "J8") (pin "1") (pinfunction "1_1") (pintype "input"))
      (node (ref "R12") (pin "2") (pinfunction "2_2") (pintype "unspecified"))
      (node (ref "R13") (pin "2") (pinfunction "2_2") (pintype "unspecified"))
      (node (ref "U3") (pin "8") (pinfunction "VB_8") (pintype "unspecified"))
    )
    (net (code "72") (name "Net-(U4-ERR)") (class "Default")
      (node (ref "C7") (pin "1") (pinfunction "1_1") (pintype "input"))
      (node (ref "U4") (pin "3") (pinfunction "ERR_3") (pintype "unspecified"))
    )
    (net (code "73") (name "Net-(U4-VB)") (class "Default")
      (node (ref "J11") (pin "1") (pinfunction "1_1") (pintype "input"))
      (node (ref "R14") (pin "2") (pinfunction "2_2") (pintype "unspecified"))
      (node (ref "R15") (pin "2") (pinfunction "2_2") (pintype "unspecified"))
      (node (ref "U4") (pin "8") (pinfunction "VB_8") (pintype "unspecified"))
    )
    (net (code "74") (name "Net-(U5-CLK)") (class "Default")
      (node (ref "P2") (pin "6") (pinfunction "6_6") (pintype "input"))
      (node (ref "U5") (pin "1") (pinfunction "CLK_1") (pintype "unspecified"))
    )
    (net (code "75") (name "Net-(U5-DT)") (class "Default")
      (node (ref "P2") (pin "5") (pinfunction "5_5") (pintype "input"))
      (node (ref "U5") (pin "2") (pinfunction "DT_2") (pintype "unspecified"))
    )
    (net (code "76") (name "Net-(U6-SCL)") (class "Default")
      (node (ref "P2") (pin "7") (pinfunction "7_7") (pintype "input"))
      (node (ref "U6") (pin "20") (pinfunction "SCL_20") (pintype "unspecified"))
    )
    (net (code "77") (name "Net-(U6-SDA)") (class "Default")
      (node (ref "P2") (pin "8") (pinfunction "8_8") (pintype "input"))
      (node (ref "U6") (pin "19") (pinfunction "SDA_19") (pintype "unspecified"))
    )
    (net (code "78") (name "Net-(U9-IN+)") (class "Default")
      (node (ref "R36") (pin "1") (pinfunction "1_1") (pintype "unspecified"))
      (node (ref "U9") (pin "3") (pinfunction "IN+_3") (pintype "unspecified"))
      (node (ref "U9") (pin "4") (pinfunction "VCC-_4") (pintype "unspecified"))
    )
    (net (code "79") (name "Net-(U9-IN-)") (class "Default")
      (node (ref "C13") (pin "2") (pinfunction "2_2") (pintype "unspecified"))
      (node (ref "R34") (pin "1") (pinfunction "1_1") (pintype "unspecified"))
      (node (ref "R35") (pin "2") (pinfunction "2_2") (pintype "unspecified"))
      (node (ref "U9") (pin "2") (pinfunction "IN-_2") (pintype "unspecified"))
    )
    (net (code "80") (name "OUT_D") (class "Default")
      (node (ref "C2") (pin "1") (pinfunction "1_1") (pintype "input"))
      (node (ref "C4") (pin "1") (pinfunction "1_1") (pintype "input"))
      (node (ref "C6") (pin "1") (pinfunction "1_1") (pintype "input"))
      (node (ref "D1") (pin "2") (pinfunction "A_2") (pintype "unspecified"))
      (node (ref "D2") (pin "2") (pinfunction "A_2") (pintype "unspecified"))
      (node (ref "J10") (pin "1") (pinfunction "1_1") (pintype "input"))
      (node (ref "J18") (pin "1") (pinfunction "1_1") (pintype "input"))
      (node (ref "Q10") (pin "2") (pinfunction "S_2") (pintype "unspecified"))
      (node (ref "Q11") (pin "3") (pinfunction "D_3") (pintype "unspecified"))
      (node (ref "R14") (pin "1") (pinfunction "1_1") (pintype "unspecified"))
      (node (ref "U1") (pin "7") (pinfunction "VCC+_7") (pintype "unspecified"))
      (node (ref "U2") (pin "1") (pinfunction "VCC_1") (pintype "unspecified"))
      (node (ref "U3") (pin "1") (pinfunction "VCC_1") (pintype "unspecified"))
      (node (ref "U4") (pin "1") (pinfunction "VCC_1") (pintype "unspecified"))
      (node (ref "U9") (pin "7") (pinfunction "VCC+_7") (pintype "unspecified"))
    )
    (net (code "81") (name "OUT_DRIVER_0") (class "Default")
      (node (ref "P4") (pin "6") (pinfunction "6_6") (pintype "input"))
      (node (ref "U2") (pin "2") (pinfunction "HIN_2") (pintype "unspecified"))
    )
    (net (code "82") (name "OUT_DRIVER_1") (class "Default")
      (node (ref "P4") (pin "7") (pinfunction "7_7") (pintype "input"))
      (node (ref "U2") (pin "3") (pinfunction "LIN_3") (pintype "unspecified"))
    )
    (net (code "83") (name "OUT_DRIVER_2") (class "Default")
      (node (ref "P4") (pin "8") (pinfunction "8_8") (pintype "input"))
      (node (ref "U3") (pin "2") (pinfunction "IN_2") (pintype "unspecified"))
    )
    (net (code "84") (name "OUT_DRIVER_3") (class "Default")
      (node (ref "P4") (pin "9") (pinfunction "9_9") (pintype "input"))
      (node (ref "U3") (pin "3") (pinfunction "SD#_3") (pintype "unspecified"))
    )
    (net (code "85") (name "OUT_DRIVER_4") (class "Default")
      (node (ref "P4") (pin "10") (pinfunction "10_10") (pintype "input"))
      (node (ref "U4") (pin "2") (pinfunction "IN_2") (pintype "unspecified"))
    )
    (net (code "86") (name "OUT_DRIVER_5") (class "Default")
      (node (ref "P4") (pin "11") (pinfunction "11_11") (pintype "input"))
      (node (ref "R1") (pin "1") (pinfunction "1_1") (pintype "unspecified"))
    )
    (net (code "87") (name "OUT_TRIANGLE") (class "Default")
      (node (ref "C13") (pin "1") (pinfunction "1_1") (pintype "unspecified"))
      (node (ref "R35") (pin "1") (pinfunction "1_1") (pintype "unspecified"))
      (node (ref "U9") (pin "6") (pinfunction "OUT_6") (pintype "unspecified"))
    )
    (net (code "88") (name "VSD_0") (class "Default")
      (node (ref "C9") (pin "1") (pinfunction "1_1") (pintype "unspecified"))
      (node (ref "P6") (pin "2") (pinfunction "2_2") (pintype "input"))
    )
    (net (code "89") (name "VSD_1") (class "Default")
      (node (ref "C10") (pin "1") (pinfunction "1_1") (pintype "unspecified"))
      (node (ref "P6") (pin "4") (pinfunction "4_4") (pintype "input"))
      (node (ref "Q7") (pin "3") (pinfunction "E_3") (pintype "unspecified"))
      (node (ref "Q8") (pin "2") (pinfunction "C_2") (pintype "unspecified"))
      (node (ref "R17") (pin "1") (pinfunction "1_1") (pintype "unspecified"))
    )
    (net (code "90") (name "VS_0") (class "Default")
      (node (ref "C1") (pin "2") (pinfunction "2_2") (pintype "input"))
      (node (ref "J6") (pin "1") (pinfunction "1_1") (pintype "input"))
      (node (ref "P11") (pin "2") (pinfunction "2_2") (pintype "unspecified"))
      (node (ref "U2") (pin "6") (pinfunction "VS_6") (pintype "unspecified"))
    )
    (net (code "91") (name "VS_1") (class "Default")
      (node (ref "C3") (pin "2") (pinfunction "2_2") (pintype "input"))
      (node (ref "J9") (pin "1") (pinfunction "1_1") (pintype "input"))
      (node (ref "P11") (pin "4") (pinfunction "4_4") (pintype "unspecified"))
      (node (ref "U3") (pin "6") (pinfunction "VS_6") (pintype "unspecified"))
    )
    (net (code "92") (name "VS_2") (class "Default")
      (node (ref "C5") (pin "2") (pinfunction "2_2") (pintype "input"))
      (node (ref "J12") (pin "1") (pinfunction "1_1") (pintype "input"))
      (node (ref "P11") (pin "6") (pinfunction "6_6") (pintype "unspecified"))
      (node (ref "U4") (pin "5") (pinfunction "VS_5") (pintype "unspecified"))
    )
    (net (code "93") (name "unconnected-(P2-Pad1)") (class "Default")
      (node (ref "P2") (pin "1") (pinfunction "1_1") (pintype "input"))
    )
    (net (code "94") (name "unconnected-(P2-Pad2)") (class "Default")
      (node (ref "P2") (pin "2") (pinfunction "2_2") (pintype "input"))
    )
    (net (code "95") (name "unconnected-(P2-Pad3)") (class "Default")
      (node (ref "P2") (pin "3") (pinfunction "3_3") (pintype "input"))
    )
    (net (code "96") (name "unconnected-(P2-Pad4)") (class "Default")
      (node (ref "P2") (pin "4") (pinfunction "4_4") (pintype "input"))
    )
    (net (code "97") (name "unconnected-(P2-Pad9)") (class "Default")
      (node (ref "P2") (pin "9") (pinfunction "9_9") (pintype "input"))
    )
    (net (code "98") (name "unconnected-(P2-Pad10)") (class "Default")
      (node (ref "P2") (pin "10") (pinfunction "10_10") (pintype "input"))
    )
    (net (code "99") (name "unconnected-(P2-Pad11)") (class "Default")
      (node (ref "P2") (pin "11") (pinfunction "11_11") (pintype "input"))
    )
    (net (code "100") (name "unconnected-(P3-Pad1)") (class "Default")
      (node (ref "P3") (pin "1") (pinfunction "1_1") (pintype "input"))
    )
    (net (code "101") (name "unconnected-(P3-Pad2)") (class "Default")
      (node (ref "P3") (pin "2") (pinfunction "2_2") (pintype "input"))
    )
    (net (code "102") (name "unconnected-(P3-Pad3)") (class "Default")
      (node (ref "P3") (pin "3") (pinfunction "3_3") (pintype "input"))
    )
    (net (code "103") (name "unconnected-(P3-Pad4)") (class "Default")
      (node (ref "P3") (pin "4") (pinfunction "4_4") (pintype "input"))
    )
    (net (code "104") (name "unconnected-(P3-Pad5)") (class "Default")
      (node (ref "P3") (pin "5") (pinfunction "5_5") (pintype "input"))
    )
    (net (code "105") (name "unconnected-(P3-Pad6)") (class "Default")
      (node (ref "P3") (pin "6") (pinfunction "6_6") (pintype "input"))
    )
    (net (code "106") (name "unconnected-(P3-Pad7)") (class "Default")
      (node (ref "P3") (pin "7") (pinfunction "7_7") (pintype "input"))
    )
    (net (code "107") (name "unconnected-(P3-Pad8)") (class "Default")
      (node (ref "P3") (pin "8") (pinfunction "8_8") (pintype "input"))
    )
    (net (code "108") (name "unconnected-(P3-Pad9)") (class "Default")
      (node (ref "P3") (pin "9") (pinfunction "9_9") (pintype "input"))
    )
    (net (code "109") (name "unconnected-(P3-Pad10)") (class "Default")
      (node (ref "P3") (pin "10") (pinfunction "10_10") (pintype "input"))
    )
    (net (code "110") (name "unconnected-(P3-Pad11)") (class "Default")
      (node (ref "P3") (pin "11") (pinfunction "11_11") (pintype "input"))
    )
    (net (code "111") (name "unconnected-(P4-Pad1)") (class "Default")
      (node (ref "P4") (pin "1") (pinfunction "1_1") (pintype "input"))
    )
    (net (code "112") (name "unconnected-(P4-Pad2)") (class "Default")
      (node (ref "P4") (pin "2") (pinfunction "2_2") (pintype "input"))
    )
    (net (code "113") (name "unconnected-(P4-Pad3)") (class "Default")
      (node (ref "P4") (pin "3") (pinfunction "3_3") (pintype "input"))
    )
    (net (code "114") (name "unconnected-(P4-Pad4)") (class "Default")
      (node (ref "P4") (pin "4") (pinfunction "4_4") (pintype "input"))
    )
    (net (code "115") (name "unconnected-(P4-Pad5)") (class "Default")
      (node (ref "P4") (pin "5") (pinfunction "5_5") (pintype "input"))
    )
    (net (code "116") (name "unconnected-(P5-Pad1)") (class "Default")
      (node (ref "P5") (pin "1") (pinfunction "1_1") (pintype "input"))
    )
    (net (code "117") (name "unconnected-(P5-Pad2)") (class "Default")
      (node (ref "P5") (pin "2") (pinfunction "2_2") (pintype "input"))
    )
    (net (code "118") (name "unconnected-(P5-Pad3)") (class "Default")
      (node (ref "P5") (pin "3") (pinfunction "3_3") (pintype "input"))
    )
    (net (code "119") (name "unconnected-(P5-Pad4)") (class "Default")
      (node (ref "P5") (pin "4") (pinfunction "4_4") (pintype "input"))
    )
    (net (code "120") (name "unconnected-(P5-Pad5)") (class "Default")
      (node (ref "P5") (pin "5") (pinfunction "5_5") (pintype "input"))
    )
    (net (code "121") (name "unconnected-(P5-Pad6)") (class "Default")
      (node (ref "P5") (pin "6") (pinfunction "6_6") (pintype "input"))
    )
    (net (code "122") (name "unconnected-(P5-Pad7)") (class "Default")
      (node (ref "P5") (pin "7") (pinfunction "7_7") (pintype "input"))
    )
    (net (code "123") (name "unconnected-(P5-Pad8)") (class "Default")
      (node (ref "P5") (pin "8") (pinfunction "8_8") (pintype "input"))
    )
    (net (code "124") (name "unconnected-(P5-Pad9)") (class "Default")
      (node (ref "P5") (pin "9") (pinfunction "9_9") (pintype "input"))
    )
    (net (code "125") (name "unconnected-(RP2-Pad3)") (class "Default")
      (node (ref "RP2") (pin "3") (pinfunction "3_3") (pintype "unspecified"))
    )
    (net (code "126") (name "unconnected-(U1-IN+-Pad3)") (class "Default")
      (node (ref "U1") (pin "3") (pinfunction "IN+_3") (pintype "unspecified"))
    )
    (net (code "127") (name "unconnected-(U1-NC-Pad8)") (class "Default")
      (node (ref "U1") (pin "8") (pinfunction "NC_8") (pintype "unspecified"))
    )
    (net (code "128") (name "unconnected-(U1-OFFSET{slash}N1-Pad1)") (class "Default")
      (node (ref "U1") (pin "1") (pinfunction "OFFSET/N1_1") (pintype "unspecified"))
    )
    (net (code "129") (name "unconnected-(U1-OFFSET{slash}N2-Pad5)") (class "Default")
      (node (ref "U1") (pin "5") (pinfunction "OFFSET/N2_5") (pintype "unspecified"))
    )
    (net (code "130") (name "unconnected-(U4-CS-Pad6)") (class "Default")
      (node (ref "U4") (pin "6") (pinfunction "CS_6") (pintype "unspecified"))
    )
    (net (code "131") (name "unconnected-(U5-SW-Pad3)") (class "Default")
      (node (ref "U5") (pin "3") (pinfunction "SW_3") (pintype "unspecified"))
    )
    (net (code "132") (name "unconnected-(U9-NC-Pad8)") (class "Default")
      (node (ref "U9") (pin "8") (pinfunction "NC_8") (pintype "unspecified"))
    )
    (net (code "133") (name "unconnected-(U9-OFFSET{slash}N1-Pad1)") (class "Default")
      (node (ref "U9") (pin "1") (pinfunction "OFFSET/N1_1") (pintype "unspecified"))
    )
    (net (code "134") (name "unconnected-(U9-OFFSET{slash}N2-Pad5)") (class "Default")
      (node (ref "U9") (pin "5") (pinfunction "OFFSET/N2_5") (pintype "unspecified"))
    )
  )
)
